# v1_mainBoard.net
KiCad netlist of a schematic drawn in EAGLE
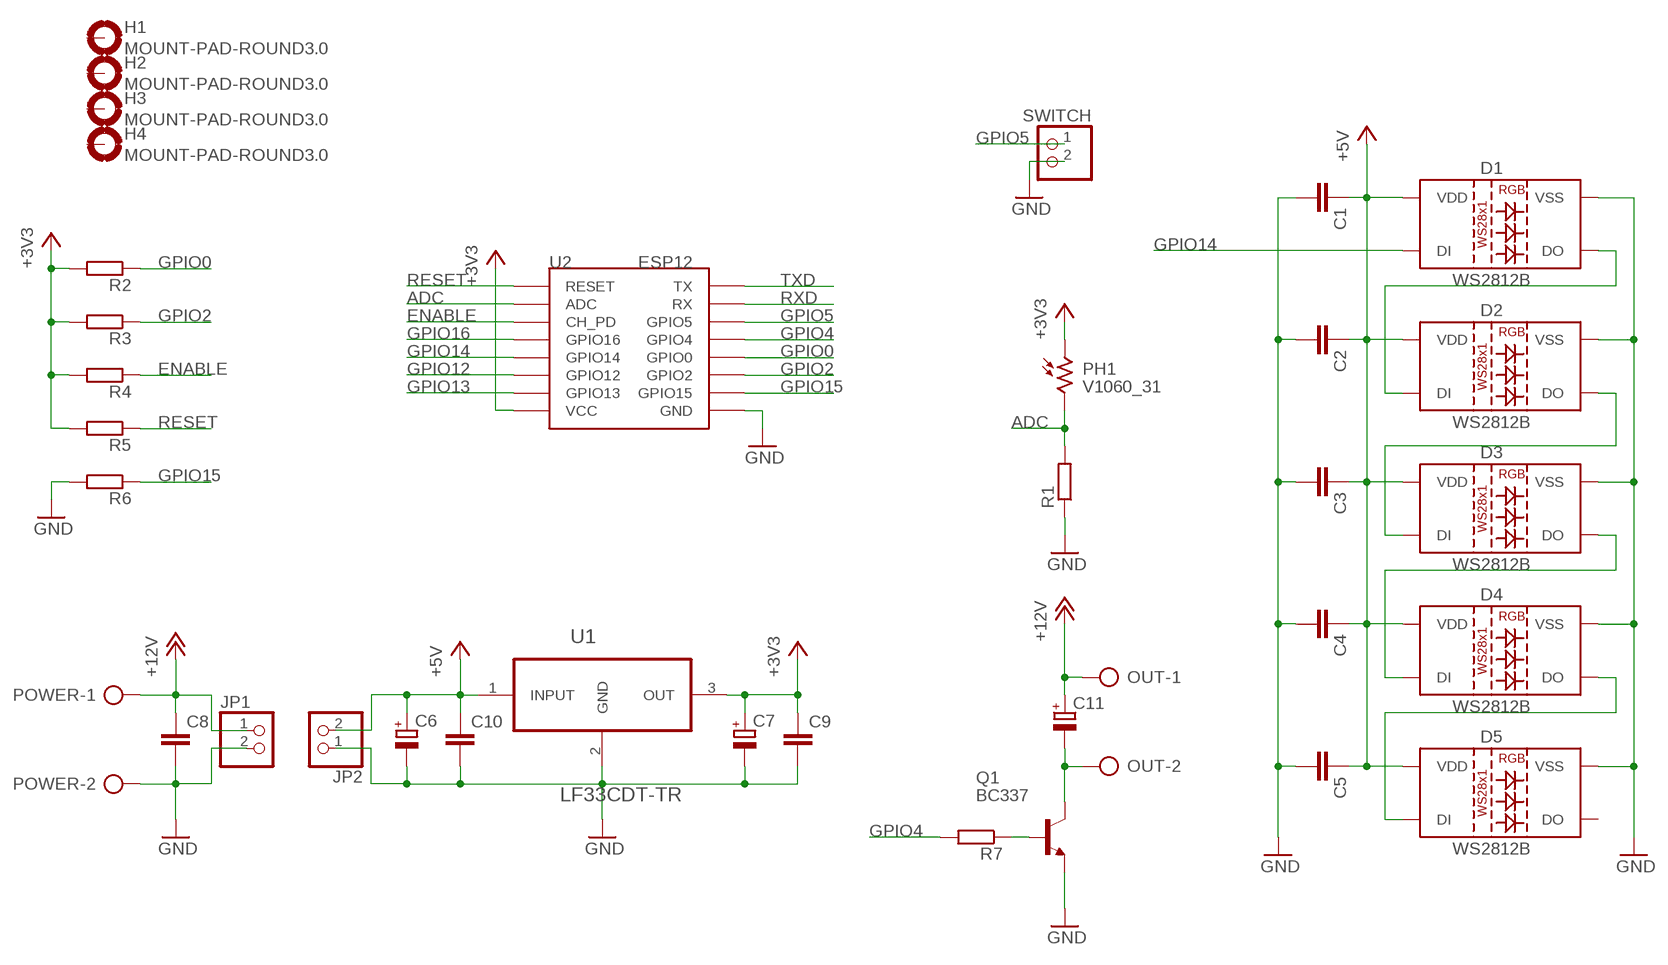
[diagram p0: schematic, sheet 1]

(export (version "E")
  (design (tool "Eeschema 10.0.6"))
  (components
    (comp (ref "C1")
      (value "C-EUC1206")
      (footprint "eagle-import:C1206")
      (libsource (lib "eagle-import") (part "C-EUC1206"))
    )
    (comp (ref "C2")
      (value "C-EUC1206")
      (footprint "eagle-import:C1206")
      (libsource (lib "eagle-import") (part "C-EUC1206"))
    )
    (comp (ref "C3")
      (value "C-EUC1206")
      (footprint "eagle-import:C1206")
      (libsource (lib "eagle-import") (part "C-EUC1206"))
    )
    (comp (ref "C4")
      (value "C-EUC1206")
      (footprint "eagle-import:C1206")
      (libsource (lib "eagle-import") (part "C-EUC1206"))
    )
    (comp (ref "C5")
      (value "C-EUC1206")
      (footprint "eagle-import:C1206")
      (libsource (lib "eagle-import") (part "C-EUC1206"))
    )
    (comp (ref "C6")
      (value "CPOL-EUE2.5-6")
      (footprint "eagle-import:E2,5-6")
      (libsource (lib "eagle-import") (part "CPOL-EUE2.5-6"))
    )
    (comp (ref "C7")
      (value "CPOL-EUE2.5-6")
      (footprint "eagle-import:E2,5-6")
      (libsource (lib "eagle-import") (part "CPOL-EUE2.5-6"))
    )
    (comp (ref "C8")
      (value "C-EUC1206")
      (footprint "eagle-import:C1206")
      (libsource (lib "eagle-import") (part "C-EUC1206"))
    )
    (comp (ref "C9")
      (value "C-EUC1206")
      (footprint "eagle-import:C1206")
      (libsource (lib "eagle-import") (part "C-EUC1206"))
    )
    (comp (ref "C10")
      (value "C-EUC1206")
      (footprint "eagle-import:C1206")
      (libsource (lib "eagle-import") (part "C-EUC1206"))
    )
    (comp (ref "C11")
      (value "CPOL-EUE3.5-8")
      (footprint "eagle-import:E3,5-8")
      (libsource (lib "eagle-import") (part "CPOL-EUE3.5-8"))
    )
    (comp (ref "D1")
      (value "WS2812B")
      (footprint "eagle-import:WS2812B")
      (fields (field (name "MF") "Worldsemi"))
      (libsource (lib "eagle-import") (part "WS2812B"))
    )
    (comp (ref "D2")
      (value "WS2812B")
      (footprint "eagle-import:WS2812B")
      (fields (field (name "MF") "Worldsemi"))
      (libsource (lib "eagle-import") (part "WS2812B"))
    )
    (comp (ref "D3")
      (value "WS2812B")
      (footprint "eagle-import:WS2812B")
      (fields (field (name "MF") "Worldsemi"))
      (libsource (lib "eagle-import") (part "WS2812B"))
    )
    (comp (ref "D4")
      (value "WS2812B")
      (footprint "eagle-import:WS2812B")
      (fields (field (name "MF") "Worldsemi"))
      (libsource (lib "eagle-import") (part "WS2812B"))
    )
    (comp (ref "D5")
      (value "WS2812B")
      (footprint "eagle-import:WS2812B")
      (fields (field (name "MF") "Worldsemi"))
      (libsource (lib "eagle-import") (part "WS2812B"))
    )
    (comp (ref "H1")
      (value "MOUNT-PAD-ROUND3.0")
      (footprint "eagle-import:3,0-PAD")
      (libsource (lib "eagle-import") (part "MOUNT-PAD-ROUND3.0"))
    )
    (comp (ref "H2")
      (value "MOUNT-PAD-ROUND3.0")
      (footprint "eagle-import:3,0-PAD")
      (libsource (lib "eagle-import") (part "MOUNT-PAD-ROUND3.0"))
    )
    (comp (ref "H3")
      (value "MOUNT-PAD-ROUND3.0")
      (footprint "eagle-import:3,0-PAD")
      (libsource (lib "eagle-import") (part "MOUNT-PAD-ROUND3.0"))
    )
    (comp (ref "H4")
      (value "MOUNT-PAD-ROUND3.0")
      (footprint "eagle-import:3,0-PAD")
      (libsource (lib "eagle-import") (part "MOUNT-PAD-ROUND3.0"))
    )
    (comp (ref "JP1")
      (value "PINHD-1X2")
      (footprint "eagle-import:1X02")
      (libsource (lib "eagle-import") (part "PINHD-1X2"))
    )
    (comp (ref "JP2")
      (value "PINHD-1X2")
      (footprint "eagle-import:1X02")
      (libsource (lib "eagle-import") (part "PINHD-1X2"))
    )
    (comp (ref "OUT")
      (value "AK300/2")
      (footprint "eagle-import:AK300_2")
      (libsource (lib "eagle-import") (part "AK300/2"))
    )
    (comp (ref "PH1")
      (value "V1060_31")
      (footprint "eagle-import:TO-5_V10")
      (libsource (lib "eagle-import") (part "?1060V_31"))
    )
    (comp (ref "POWER")
      (value "AK300/2")
      (footprint "eagle-import:AK300_2")
      (libsource (lib "eagle-import") (part "AK300/2"))
    )
    (comp (ref "Q1")
      (value "BC337")
      (footprint "eagle-import:TO92")
      (libsource (lib "eagle-import") (part "BC337"))
    )
    (comp (ref "R1")
      (value "R-EU_R1206")
      (footprint "eagle-import:R1206")
      (libsource (lib "eagle-import") (part "R-EU_R1206"))
    )
    (comp (ref "R2")
      (value "R-EU_R1206")
      (footprint "eagle-import:R1206")
      (libsource (lib "eagle-import") (part "R-EU_R1206"))
    )
    (comp (ref "R3")
      (value "R-EU_R1206")
      (footprint "eagle-import:R1206")
      (libsource (lib "eagle-import") (part "R-EU_R1206"))
    )
    (comp (ref "R4")
      (value "R-EU_R1206")
      (footprint "eagle-import:R1206")
      (libsource (lib "eagle-import") (part "R-EU_R1206"))
    )
    (comp (ref "R5")
      (value "R-EU_R1206")
      (footprint "eagle-import:R1206")
      (libsource (lib "eagle-import") (part "R-EU_R1206"))
    )
    (comp (ref "R6")
      (value "R-EU_R1206")
      (footprint "eagle-import:R1206")
      (libsource (lib "eagle-import") (part "R-EU_R1206"))
    )
    (comp (ref "R7")
      (value "R-EU_R1206")
      (footprint "eagle-import:R1206")
      (libsource (lib "eagle-import") (part "R-EU_R1206"))
    )
    (comp (ref "SWITCH")
      (value "PINHD-1X2")
      (footprint "eagle-import:1X02")
      (libsource (lib "eagle-import") (part "PINHD-1X2"))
    )
    (comp (ref "U1")
      (value "LF33CDT-TR")
      (footprint "eagle-import:TO228P972X240-3N")
      (fields (field (name "MF") "STMicroelectronics"))
      (libsource (lib "eagle-import") (part "LF33CDT-TR"))
    )
    (comp (ref "U2")
      (value "ESP12")
      (footprint "eagle-import:ESP12")
      (libsource (lib "eagle-import") (part "ESP12"))
    )
  )
  (nets
    (net (code "1") (name "+3V3") (class "Default")
      (node (ref "C7") (pin "+") (pinfunction "+_+") (pintype "passive"))
      (node (ref "C9") (pin "1") (pinfunction "1_1") (pintype "passive"))
      (node (ref "PH1") (pin "1") (pinfunction "1_1") (pintype "passive"))
      (node (ref "R2") (pin "2") (pinfunction "2_2") (pintype "passive"))
      (node (ref "R3") (pin "2") (pinfunction "2_2") (pintype "passive"))
      (node (ref "R4") (pin "2") (pinfunction "2_2") (pintype "passive"))
      (node (ref "R5") (pin "2") (pinfunction "2_2") (pintype "passive"))
      (node (ref "U1") (pin "3") (pinfunction "OUT_3") (pintype "output"))
      (node (ref "U2") (pin "VCC") (pinfunction "VCC_VCC") (pintype "bidirectional"))
    )
    (net (code "2") (name "+5V") (class "Default")
      (node (ref "C1") (pin "1") (pinfunction "1_1") (pintype "passive"))
      (node (ref "C10") (pin "1") (pinfunction "1_1") (pintype "passive"))
      (node (ref "C2") (pin "1") (pinfunction "1_1") (pintype "passive"))
      (node (ref "C3") (pin "1") (pinfunction "1_1") (pintype "passive"))
      (node (ref "C4") (pin "1") (pinfunction "1_1") (pintype "passive"))
      (node (ref "C5") (pin "1") (pinfunction "1_1") (pintype "passive"))
      (node (ref "C6") (pin "+") (pinfunction "+_+") (pintype "passive"))
      (node (ref "D1") (pin "1") (pinfunction "VDD_1") (pintype "bidirectional"))
      (node (ref "D2") (pin "1") (pinfunction "VDD_1") (pintype "bidirectional"))
      (node (ref "D3") (pin "1") (pinfunction "VDD_1") (pintype "bidirectional"))
      (node (ref "D4") (pin "1") (pinfunction "VDD_1") (pintype "bidirectional"))
      (node (ref "D5") (pin "1") (pinfunction "VDD_1") (pintype "bidirectional"))
      (node (ref "JP2") (pin "2") (pinfunction "2_2") (pintype "passive"))
      (node (ref "U1") (pin "1") (pinfunction "INPUT_1") (pintype "input"))
    )
    (net (code "3") (name "+12V") (class "Default")
      (node (ref "C11") (pin "+") (pinfunction "+_+") (pintype "passive"))
      (node (ref "C8") (pin "1") (pinfunction "1_1") (pintype "passive"))
      (node (ref "JP1") (pin "1") (pinfunction "1_1") (pintype "passive"))
      (node (ref "OUT") (pin "1") (pinfunction "KL_1") (pintype "passive"))
      (node (ref "POWER") (pin "1") (pinfunction "KL_1") (pintype "passive"))
    )
    (net (code "4") (name "/ADC") (class "Default")
      (node (ref "PH1") (pin "2") (pinfunction "2_2") (pintype "passive"))
      (node (ref "R1") (pin "2") (pinfunction "2_2") (pintype "passive"))
      (node (ref "U2") (pin "ADC") (pinfunction "ADC_ADC") (pintype "bidirectional"))
    )
    (net (code "5") (name "/ENABLE") (class "Default")
      (node (ref "R4") (pin "1") (pinfunction "1_1") (pintype "passive"))
      (node (ref "U2") (pin "CH_PD") (pinfunction "CH_PD_CH_PD") (pintype "bidirectional"))
    )
    (net (code "6") (name "/GPIO0") (class "Default")
      (node (ref "R2") (pin "1") (pinfunction "1_1") (pintype "passive"))
      (node (ref "U2") (pin "GPIO0") (pinfunction "GPIO0_GPIO0") (pintype "bidirectional"))
    )
    (net (code "7") (name "/GPIO2") (class "Default")
      (node (ref "R3") (pin "1") (pinfunction "1_1") (pintype "passive"))
      (node (ref "U2") (pin "GPIO2") (pinfunction "GPIO2_GPIO2") (pintype "bidirectional"))
    )
    (net (code "8") (name "/GPIO4") (class "Default")
      (node (ref "R7") (pin "2") (pinfunction "2_2") (pintype "passive"))
      (node (ref "U2") (pin "GPIO5") (pinfunction "GPIO4_GPIO5") (pintype "bidirectional"))
    )
    (net (code "9") (name "/GPIO5") (class "Default")
      (node (ref "SWITCH") (pin "1") (pinfunction "1_1") (pintype "passive"))
      (node (ref "U2") (pin "GPIO4") (pinfunction "GPIO5_GPIO4") (pintype "bidirectional"))
    )
    (net (code "10") (name "/GPIO12") (class "Default")
      (node (ref "U2") (pin "GPIO12") (pinfunction "GPIO12_GPIO12") (pintype "bidirectional"))
    )
    (net (code "11") (name "/GPIO13") (class "Default")
      (node (ref "U2") (pin "GPIO13") (pinfunction "GPIO13_GPIO13") (pintype "bidirectional"))
    )
    (net (code "12") (name "/GPIO14") (class "Default")
      (node (ref "D1") (pin "4") (pinfunction "DI_4") (pintype "bidirectional"))
      (node (ref "U2") (pin "GPIO14") (pinfunction "GPIO14_GPIO14") (pintype "bidirectional"))
    )
    (net (code "13") (name "/GPIO15") (class "Default")
      (node (ref "R6") (pin "1") (pinfunction "1_1") (pintype "passive"))
      (node (ref "U2") (pin "GPIO15") (pinfunction "GPIO15_GPIO15") (pintype "bidirectional"))
    )
    (net (code "14") (name "/GPIO16") (class "Default")
      (node (ref "U2") (pin "GPIO16") (pinfunction "GPIO16_GPIO16") (pintype "bidirectional"))
    )
    (net (code "15") (name "/RESET") (class "Default")
      (node (ref "R5") (pin "1") (pinfunction "1_1") (pintype "passive"))
      (node (ref "U2") (pin "RESET") (pinfunction "RESET_RESET") (pintype "bidirectional"))
    )
    (net (code "16") (name "/RXD") (class "Default")
      (node (ref "U2") (pin "RX") (pinfunction "RX_RX") (pintype "bidirectional"))
    )
    (net (code "17") (name "/TXD") (class "Default")
      (node (ref "U2") (pin "TX") (pinfunction "TX_TX") (pintype "bidirectional"))
    )
    (net (code "18") (name "GND") (class "Default")
      (node (ref "C1") (pin "2") (pinfunction "2_2") (pintype "passive"))
      (node (ref "C10") (pin "2") (pinfunction "2_2") (pintype "passive"))
      (node (ref "C2") (pin "2") (pinfunction "2_2") (pintype "passive"))
      (node (ref "C3") (pin "2") (pinfunction "2_2") (pintype "passive"))
      (node (ref "C4") (pin "2") (pinfunction "2_2") (pintype "passive"))
      (node (ref "C5") (pin "2") (pinfunction "2_2") (pintype "passive"))
      (node (ref "C6") (pin "-") (pinfunction "-_-") (pintype "passive"))
      (node (ref "C7") (pin "-") (pinfunction "-_-") (pintype "passive"))
      (node (ref "C8") (pin "2") (pinfunction "2_2") (pintype "passive"))
      (node (ref "C9") (pin "2") (pinfunction "2_2") (pintype "passive"))
      (node (ref "D1") (pin "3") (pinfunction "VSS_3") (pintype "bidirectional"))
      (node (ref "D2") (pin "3") (pinfunction "VSS_3") (pintype "bidirectional"))
      (node (ref "D3") (pin "3") (pinfunction "VSS_3") (pintype "bidirectional"))
      (node (ref "D4") (pin "3") (pinfunction "VSS_3") (pintype "bidirectional"))
      (node (ref "D5") (pin "3") (pinfunction "VSS_3") (pintype "bidirectional"))
      (node (ref "JP1") (pin "2") (pinfunction "2_2") (pintype "passive"))
      (node (ref "JP2") (pin "1") (pinfunction "1_1") (pintype "passive"))
      (node (ref "POWER") (pin "2") (pinfunction "KL_2") (pintype "passive"))
      (node (ref "Q1") (pin "1") (pinfunction "E_1") (pintype "passive"))
      (node (ref "R1") (pin "1") (pinfunction "1_1") (pintype "passive"))
      (node (ref "R6") (pin "2") (pinfunction "2_2") (pintype "passive"))
      (node (ref "SWITCH") (pin "2") (pinfunction "2_2") (pintype "passive"))
      (node (ref "U1") (pin "2") (pinfunction "GND_2") (pintype "passive"))
      (node (ref "U2") (pin "GND") (pinfunction "GND_GND") (pintype "bidirectional"))
    )
    (net (code "19") (name "Net-(D1-DO)") (class "Default")
      (node (ref "D1") (pin "2") (pinfunction "DO_2") (pintype "bidirectional"))
      (node (ref "D2") (pin "4") (pinfunction "DI_4") (pintype "bidirectional"))
    )
    (net (code "20") (name "Net-(D2-DO)") (class "Default")
      (node (ref "D2") (pin "2") (pinfunction "DO_2") (pintype "bidirectional"))
      (node (ref "D3") (pin "4") (pinfunction "DI_4") (pintype "bidirectional"))
    )
    (net (code "21") (name "Net-(D3-DO)") (class "Default")
      (node (ref "D3") (pin "2") (pinfunction "DO_2") (pintype "bidirectional"))
      (node (ref "D4") (pin "4") (pinfunction "DI_4") (pintype "bidirectional"))
    )
    (net (code "22") (name "Net-(D4-DO)") (class "Default")
      (node (ref "D4") (pin "2") (pinfunction "DO_2") (pintype "bidirectional"))
      (node (ref "D5") (pin "4") (pinfunction "DI_4") (pintype "bidirectional"))
    )
    (net (code "23") (name "Net-(OUTB-KL)") (class "Default")
      (node (ref "C11") (pin "-") (pinfunction "-_-") (pintype "passive"))
      (node (ref "OUT") (pin "2") (pinfunction "KL_2") (pintype "passive"))
      (node (ref "Q1") (pin "3") (pinfunction "C_3") (pintype "passive"))
    )
    (net (code "24") (name "Net-(Q1-B)") (class "Default")
      (node (ref "Q1") (pin "2") (pinfunction "B_2") (pintype "passive"))
      (node (ref "R7") (pin "1") (pinfunction "1_1") (pintype "passive"))
    )
    (net (code "25") (name "unconnected-(D5-DO-Pad2)") (class "Default")
      (node (ref "D5") (pin "2") (pinfunction "DO_2") (pintype "bidirectional"))
    )
    (net (code "26") (name "unconnected-(H1-MOUNT-PadB3,0)") (class "Default")
      (node (ref "H1") (pin "B3,0") (pinfunction "MOUNT_B3,0") (pintype "passive"))
    )
    (net (code "27") (name "unconnected-(H2-MOUNT-PadB3,0)") (class "Default")
      (node (ref "H2") (pin "B3,0") (pinfunction "MOUNT_B3,0") (pintype "passive"))
    )
    (net (code "28") (name "unconnected-(H3-MOUNT-PadB3,0)") (class "Default")
      (node (ref "H3") (pin "B3,0") (pinfunction "MOUNT_B3,0") (pintype "passive"))
    )
    (net (code "29") (name "unconnected-(H4-MOUNT-PadB3,0)") (class "Default")
      (node (ref "H4") (pin "B3,0") (pinfunction "MOUNT_B3,0") (pintype "passive"))
    )
  )
)
